# SimGEKI2_AudioPort.net
KiCad netlist of a schematic drawn in EasyEDA Pro
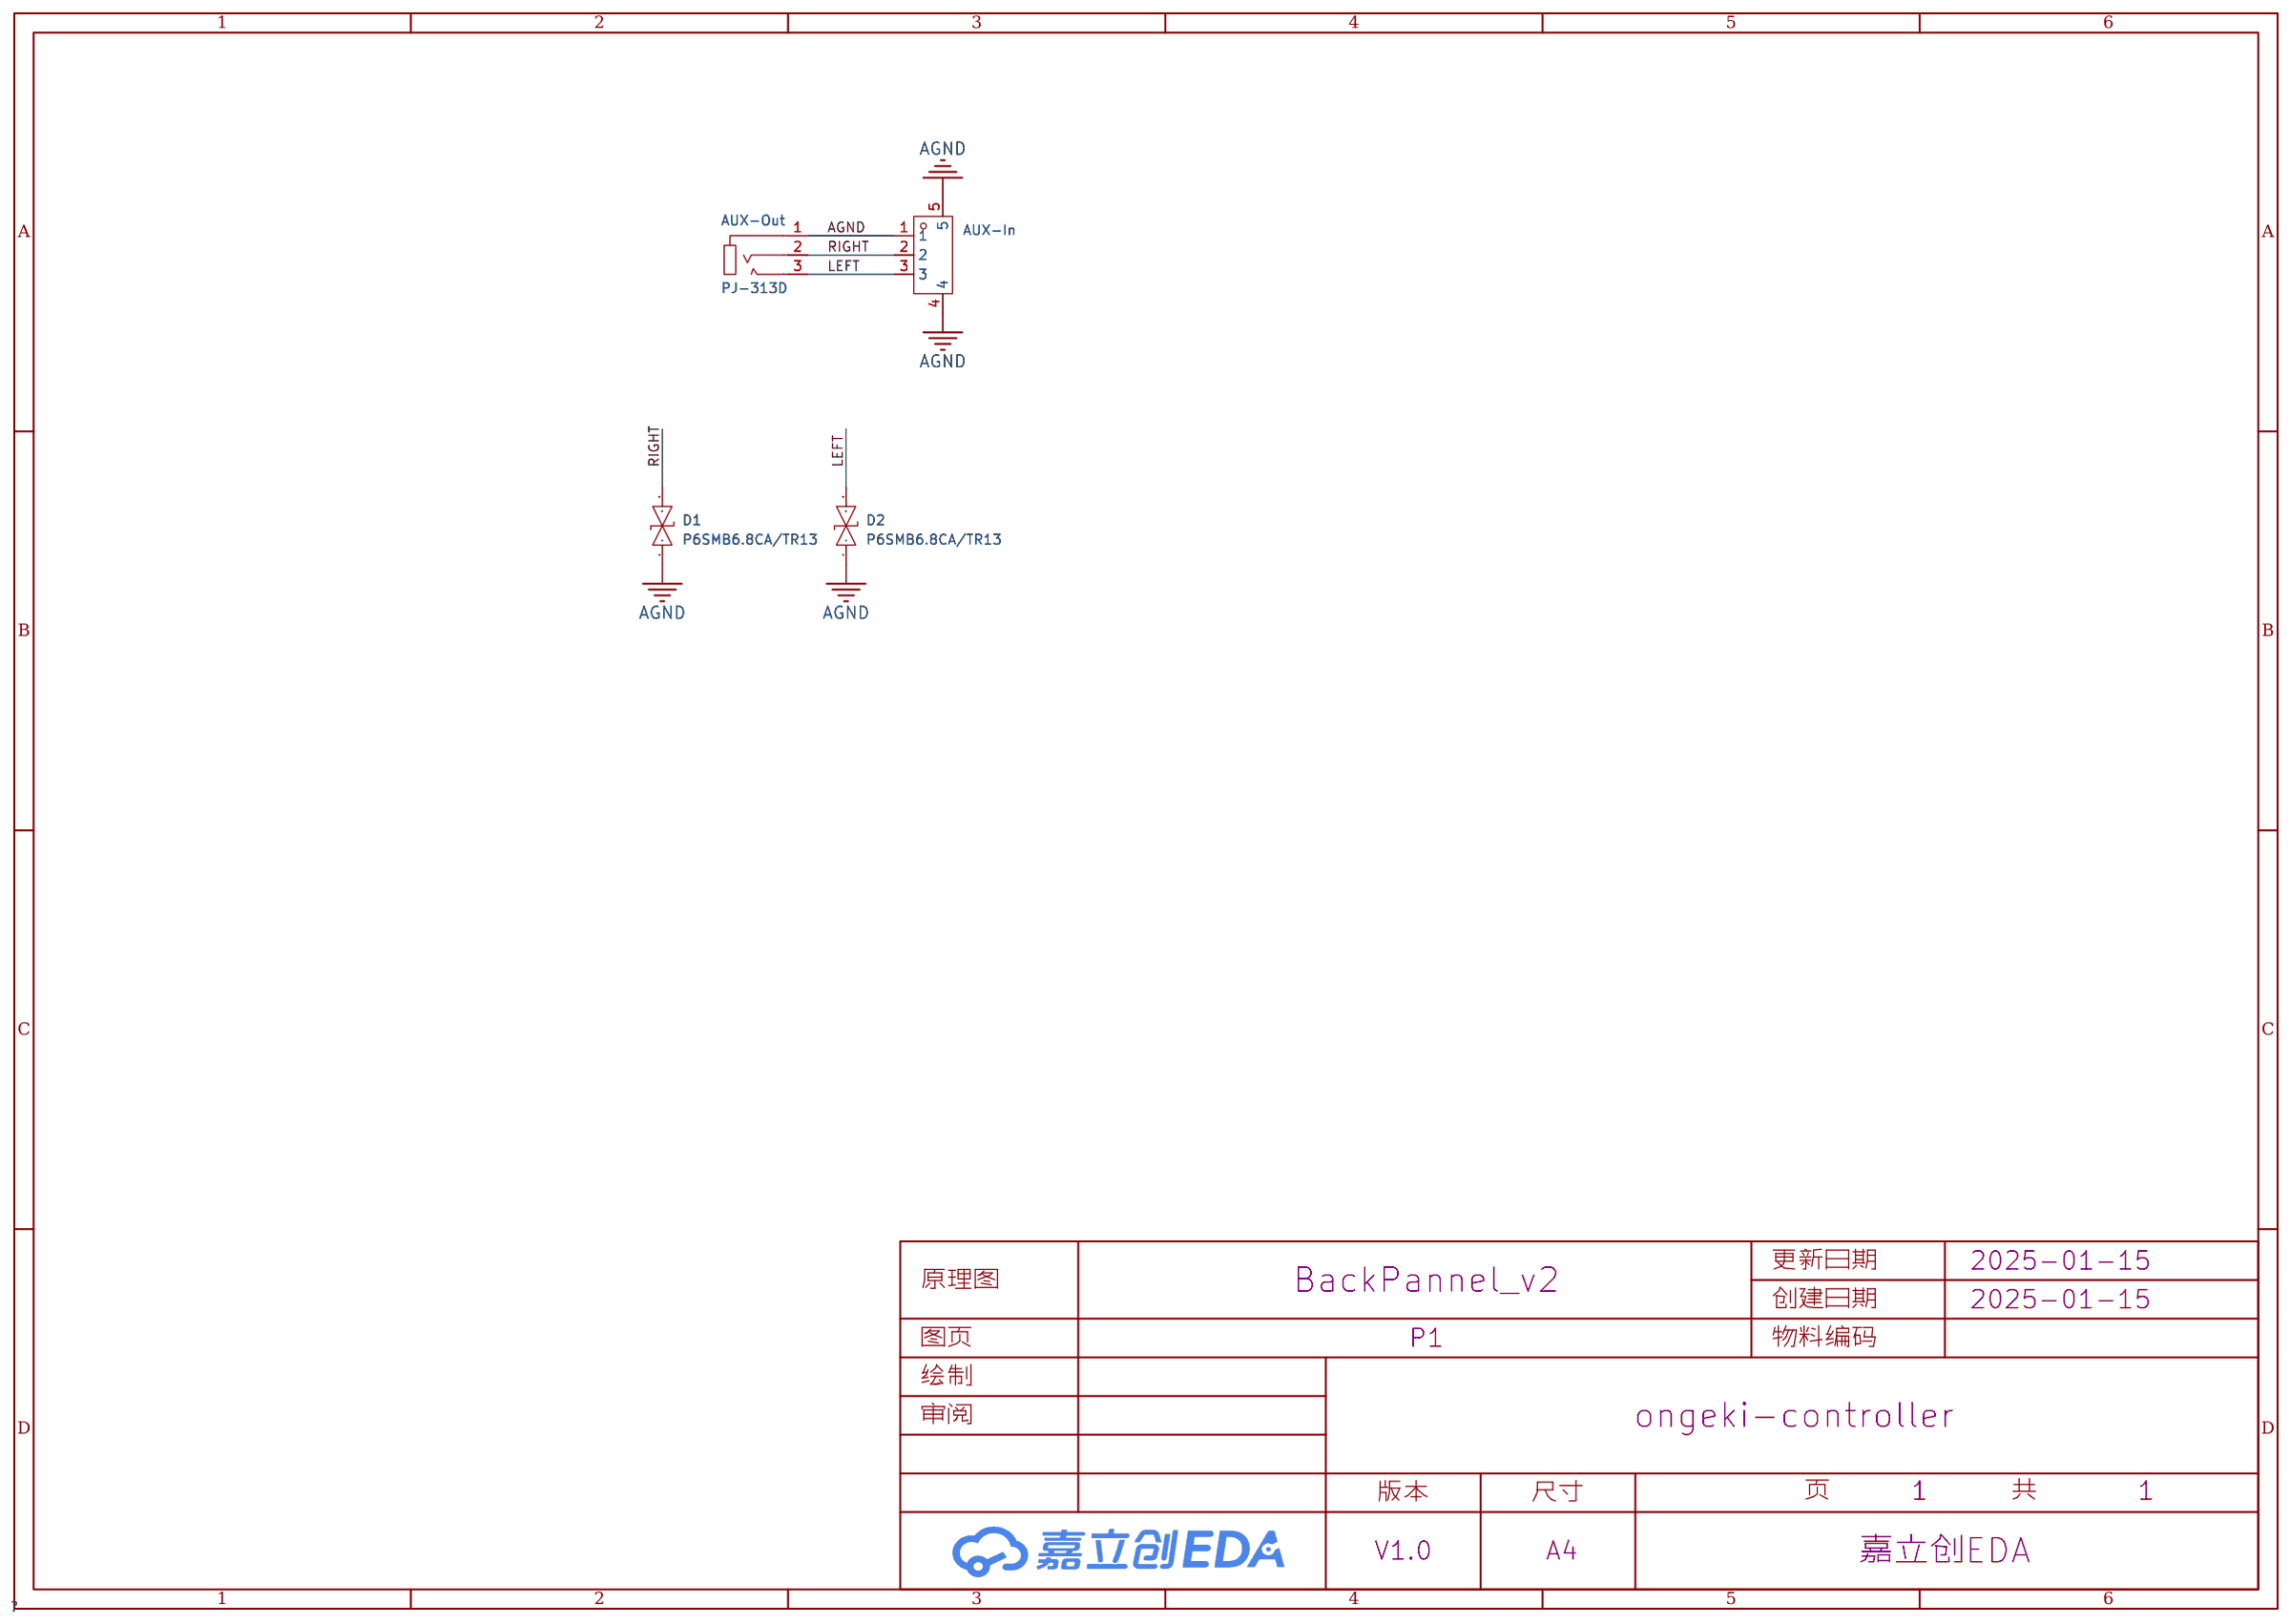
[diagram p0: schematic sheet]

(export (version "E")
  (design (tool "Eeschema 10.0.6"))
  (components
    (comp (ref "AUX-In")
      (value "WAFER-PH2.0-3PWB")
      (footprint "easyedapro:CONN-SMD_3P-P2.00_XUNPU_WAFER-PH2.0-3PWB")
      (description "插针结构:1x3P;间距:2mm;安装方式:卧贴;总PIN数:3P;排数:1;每排PIN数:3;额定电流:2A;工作温度范围:-25°C~+85°C;")
      (fields (field (name "Manufacturer") "XUNPU(讯普)"))
      (libsource (lib "easyedapro") (part "WAFER-PH2.0-3PWB"))
    )
    (comp (ref "AUX-Out")
      (value "PJ-313D")
      (footprint "easyedapro:AUDIO-SMD_PJ-313D-2")
      (description "连接器类型:3.5mm耳机座;额定电流:500mA;额定电压:30V;工作温度范围:-30°C~+70°C;")
      (fields (field (name "Manufacturer") "SHOU HAN(首韩)"))
      (libsource (lib "easyedapro") (part "PJ-313D_C668608"))
    )
    (comp (ref "D1")
      (value "P6SMB6.8CA/TR13")
      (footprint "easyedapro:SMB_L4.6-W3.6-LS5.3-BI")
      (description "反向截止电压(Vrwm):5.8V;钳位电压:10.5V;峰值脉冲电流(Ipp):58.1A;峰值脉冲功率(Ppp):600W;击穿电压:6.45V;")
      (fields (field (name "Manufacturer") "Brightking(君耀电子)"))
      (libsource (lib "easyedapro") (part "P6SMB6.8CA-C78395"))
    )
    (comp (ref "D2")
      (value "P6SMB6.8CA/TR13")
      (footprint "easyedapro:SMB_L4.6-W3.6-LS5.3-BI")
      (description "反向截止电压(Vrwm):5.8V;钳位电压:10.5V;峰值脉冲电流(Ipp):58.1A;峰值脉冲功率(Ppp):600W;击穿电压:6.45V;")
      (fields (field (name "Manufacturer") "Brightking(君耀电子)"))
      (libsource (lib "easyedapro") (part "P6SMB6.8CA-C78395"))
    )
  )
  (nets
    (net (code "1") (name "/LEFT") (class "Default")
      (node (ref "AUX-In") (pin "3") (pinfunction "3_3") (pintype "unspecified"))
      (node (ref "AUX-Out") (pin "3") (pinfunction "3_3") (pintype "unspecified"))
      (node (ref "D2") (pin "2") (pinfunction "2_2") (pintype "unspecified"))
    )
    (net (code "2") (name "/RIGHT") (class "Default")
      (node (ref "AUX-In") (pin "2") (pinfunction "2_2") (pintype "unspecified"))
      (node (ref "AUX-Out") (pin "2") (pinfunction "2_2") (pintype "unspecified"))
      (node (ref "D1") (pin "2") (pinfunction "2_2") (pintype "unspecified"))
    )
    (net (code "3") (name "AGND") (class "Default")
      (node (ref "AUX-In") (pin "1") (pinfunction "1_1") (pintype "unspecified"))
      (node (ref "AUX-In") (pin "4") (pinfunction "4_4") (pintype "unspecified"))
      (node (ref "AUX-In") (pin "5") (pinfunction "5_5") (pintype "unspecified"))
      (node (ref "AUX-Out") (pin "1") (pinfunction "1_1") (pintype "unspecified"))
      (node (ref "D1") (pin "1") (pinfunction "1_1") (pintype "unspecified"))
      (node (ref "D2") (pin "1") (pinfunction "1_1") (pintype "unspecified"))
    )
  )
)
